# Adafruit_MicroLipo.net
KiCad netlist of a schematic drawn in EAGLE
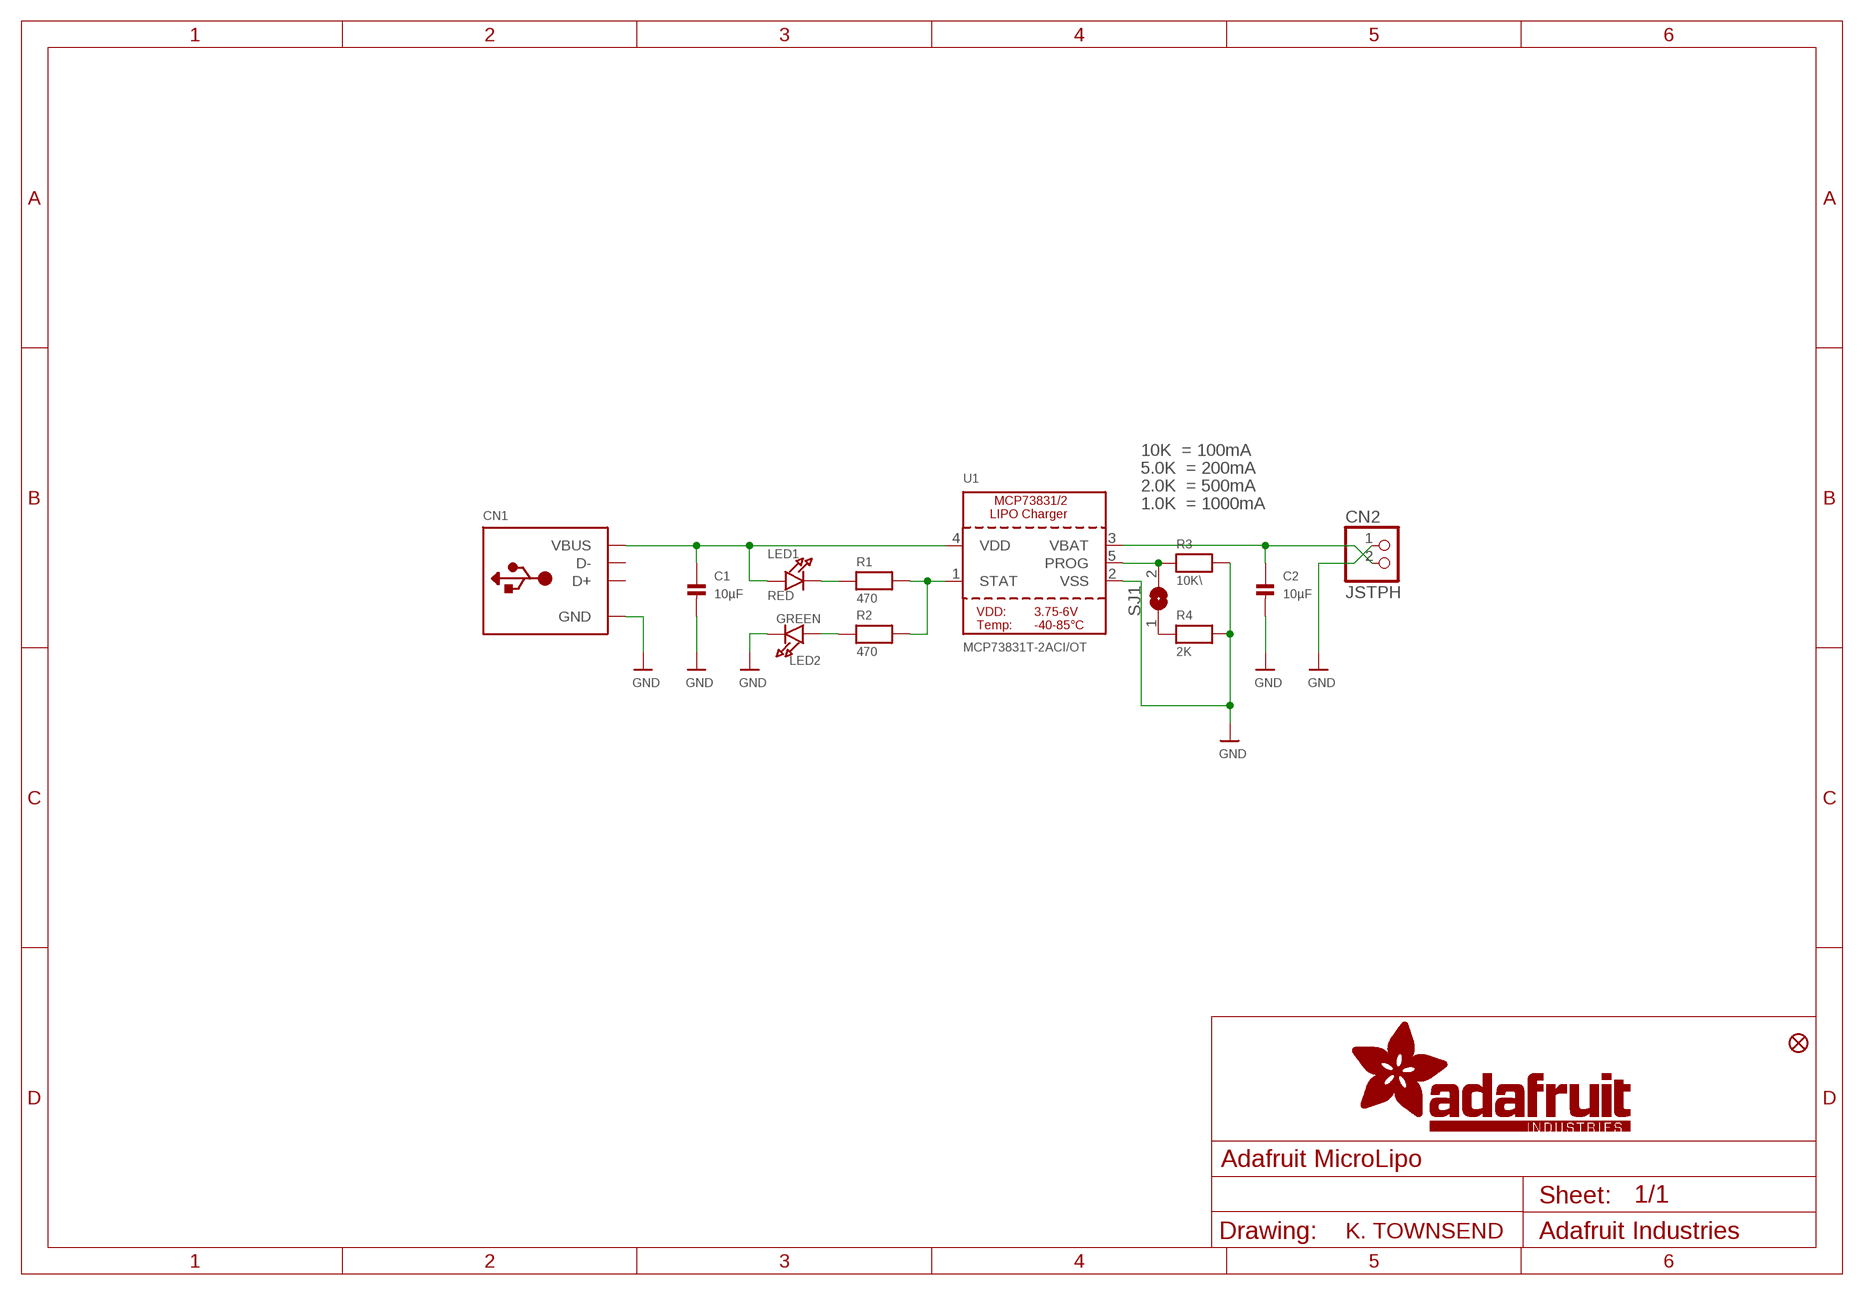
[diagram p0: schematic, sheet 1]

(export (version "E")
  (design (tool "Eeschema 10.0.6"))
  (components
    (comp (ref "C1")
      (value "10µF")
      (footprint "eagle-import:0805")
      (libsource (lib "eagle-import") (part "CAP_CERAMIC0805"))
    )
    (comp (ref "C2")
      (value "10µF")
      (footprint "eagle-import:0805")
      (libsource (lib "eagle-import") (part "CAP_CERAMIC0805"))
    )
    (comp (ref "CN1")
      (value "USB_TYPEAPCB")
      (footprint "eagle-import:USBA_PCB")
      (libsource (lib "eagle-import") (part "USB_TYPEAPCB"))
    )
    (comp (ref "CN2")
      (value "JSTPH")
      (footprint "eagle-import:JSTPH2")
      (libsource (lib "eagle-import") (part "JST_2PIN"))
    )
    (comp (ref "FID1")
      (value "FIDUCIAL\"\"")
      (footprint "eagle-import:FIDUCIAL_1MM")
      (libsource (lib "eagle-import") (part "FIDUCIAL{dblquote}{dblquote}"))
    )
    (comp (ref "LED1")
      (value "RED")
      (footprint "eagle-import:CHIPLED_0805")
      (libsource (lib "eagle-import") (part "LED0805"))
    )
    (comp (ref "LED2")
      (value "GREEN")
      (footprint "eagle-import:CHIPLED_0805")
      (libsource (lib "eagle-import") (part "LED0805"))
    )
    (comp (ref "R1")
      (value "470")
      (footprint "eagle-import:0805")
      (libsource (lib "eagle-import") (part "RESISTOR0805"))
    )
    (comp (ref "R2")
      (value "470")
      (footprint "eagle-import:0805")
      (libsource (lib "eagle-import") (part "RESISTOR0805"))
    )
    (comp (ref "R3")
      (value "10K\\")
      (footprint "eagle-import:0805")
      (libsource (lib "eagle-import") (part "RESISTOR0805"))
    )
    (comp (ref "R4")
      (value "2K")
      (footprint "eagle-import:0805")
      (libsource (lib "eagle-import") (part "RESISTOR0805"))
    )
    (comp (ref "SJ1")
      (value "SOLDERJUMPER")
      (footprint "eagle-import:SOLDERJUMPER_ARROW_NOPASTE")
      (libsource (lib "eagle-import") (part "SOLDERJUMPER"))
    )
    (comp (ref "U1")
      (value "MCP73831T-2ACI/OT")
      (footprint "eagle-import:SOT23-5")
      (libsource (lib "eagle-import") (part "MCP73831/2"))
    )
  )
  (nets
    (net (code "1") (name "GND") (class "Default")
      (node (ref "C1") (pin "2") (pinfunction "P$2_2") (pintype "passive"))
      (node (ref "C2") (pin "2") (pinfunction "P$2_2") (pintype "passive"))
      (node (ref "CN1") (pin "GND") (pinfunction "GND_GND") (pintype "power_in"))
      (node (ref "CN2") (pin "1") (pinfunction "1_1") (pintype "passive"))
      (node (ref "LED2") (pin "C") (pinfunction "C_C") (pintype "passive"))
      (node (ref "R3") (pin "2") (pinfunction "2_2") (pintype "passive"))
      (node (ref "R4") (pin "2") (pinfunction "2_2") (pintype "passive"))
      (node (ref "U1") (pin "2") (pinfunction "VSS_2") (pintype "power_in"))
    )
    (net (code "2") (name "Net-(C1-P$1)") (class "Default")
      (node (ref "C1") (pin "1") (pinfunction "P$1_1") (pintype "passive"))
      (node (ref "CN1") (pin "VCC") (pinfunction "VBUS_VCC") (pintype "power_in"))
      (node (ref "LED1") (pin "A") (pinfunction "A_A") (pintype "passive"))
      (node (ref "U1") (pin "4") (pinfunction "VDD_4") (pintype "power_in"))
    )
    (net (code "3") (name "Net-(C2-P$1)") (class "Default")
      (node (ref "C2") (pin "1") (pinfunction "P$1_1") (pintype "passive"))
      (node (ref "CN2") (pin "2") (pinfunction "2_2") (pintype "passive"))
      (node (ref "U1") (pin "3") (pinfunction "VBAT_3") (pintype "power_in"))
    )
    (net (code "4") (name "Net-(LED1-PadC)") (class "Default")
      (node (ref "LED1") (pin "C") (pinfunction "C_C") (pintype "passive"))
      (node (ref "R1") (pin "1") (pinfunction "1_1") (pintype "passive"))
    )
    (net (code "5") (name "Net-(LED2-PadA)") (class "Default")
      (node (ref "LED2") (pin "A") (pinfunction "A_A") (pintype "passive"))
      (node (ref "R2") (pin "1") (pinfunction "1_1") (pintype "passive"))
    )
    (net (code "6") (name "Net-(R4-Pad1)") (class "Default")
      (node (ref "R4") (pin "1") (pinfunction "1_1") (pintype "passive"))
      (node (ref "SJ1") (pin "1") (pinfunction "1_1") (pintype "passive"))
    )
    (net (code "7") (name "Net-(U1-PROG)") (class "Default")
      (node (ref "R3") (pin "1") (pinfunction "1_1") (pintype "passive"))
      (node (ref "SJ1") (pin "2") (pinfunction "2_2") (pintype "passive"))
      (node (ref "U1") (pin "5") (pinfunction "PROG_5") (pintype "input"))
    )
    (net (code "8") (name "Net-(U1-STAT)") (class "Default")
      (node (ref "R1") (pin "2") (pinfunction "2_2") (pintype "passive"))
      (node (ref "R2") (pin "2") (pinfunction "2_2") (pintype "passive"))
      (node (ref "U1") (pin "1") (pinfunction "STAT_1") (pintype "output"))
    )
    (net (code "9") (name "unconnected-(CN1-D+-PadUSB_PLUS)") (class "Default")
      (node (ref "CN1") (pin "USB_PLUS") (pinfunction "D+_USB_PLUS") (pintype "bidirectional"))
    )
    (net (code "10") (name "unconnected-(CN1-D--PadUSB_NEG)") (class "Default")
      (node (ref "CN1") (pin "USB_NEG") (pinfunction "D-_USB_NEG") (pintype "bidirectional"))
    )
  )
)
